# ESP32_XPID.net
KiCad netlist of a schematic drawn in Altium Designer
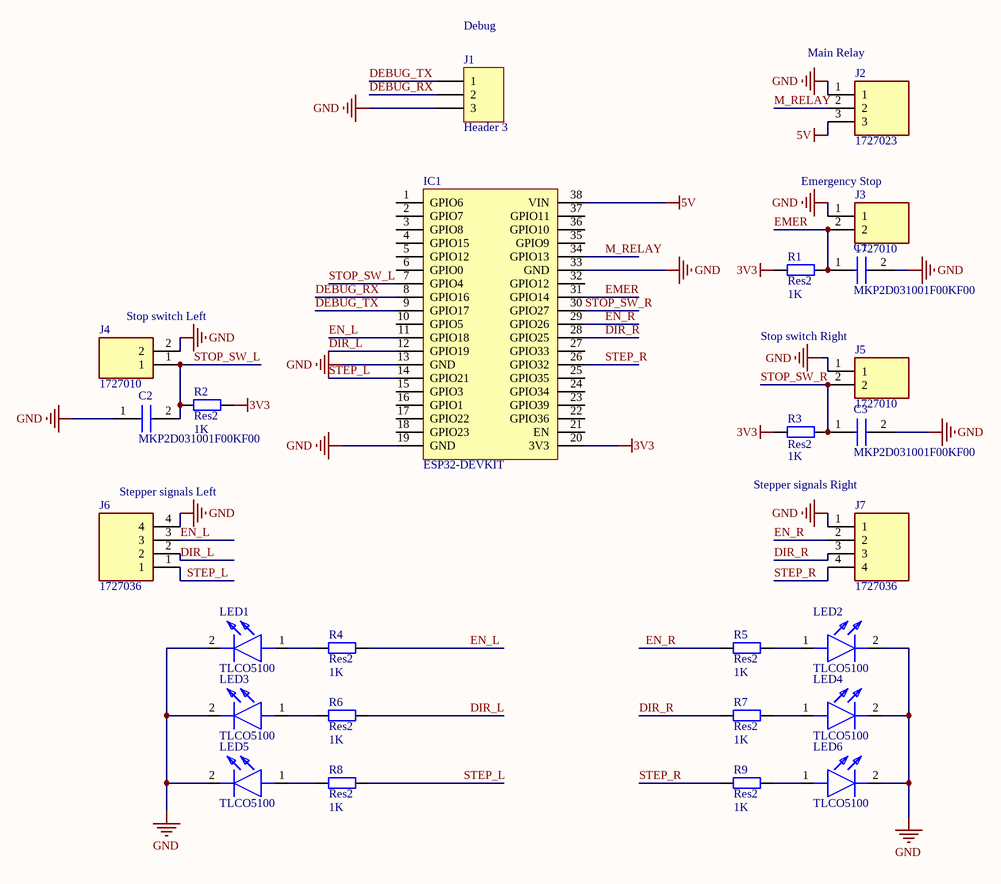
[diagram p0: ESP32_XPID.SchDoc]

(export (version "E")
  (design (tool "Eeschema 10.0.6"))
  (components
    (comp (ref "C1")
      (value "MKP2D031001F00KF00")
      (footprint "SamacSys:MKP2D031001F00KF00")
      (description "Capacitor")
      (fields (field (name "MOUSER PART NUMBER") "505-MKP2D031001F00KF"))
      (libsource (lib "*") (part "MKP2D031001F00KF00"))
    )
    (comp (ref "C2")
      (value "MKP2D031001F00KF00")
      (footprint "SamacSys:MKP2D031001F00KF00")
      (description "Capacitor")
      (fields (field (name "MOUSER PART NUMBER") "505-MKP2D031001F00KF"))
      (libsource (lib "*") (part "MKP2D031001F00KF00"))
    )
    (comp (ref "C3")
      (value "MKP2D031001F00KF00")
      (footprint "SamacSys:MKP2D031001F00KF00")
      (description "Capacitor")
      (fields (field (name "MOUSER PART NUMBER") "505-MKP2D031001F00KF"))
      (libsource (lib "*") (part "MKP2D031001F00KF00"))
    )
    (comp (ref "IC1")
      (value "ESP32-DEVKIT")
      (footprint "NODEMCU-32S")
      (description "NODE-MCU ESP32 development kit")
      (libsource (lib "ESP32_XPID") (part "NODE-MCU-32S"))
    )
    (comp (ref "J1")
      (value "Header 3")
      (footprint "HDR1X3")
      (description "Header, 3-Pin")
      (fields (field (name "PUBLISHER") "Altium Limited"))
      (libsource (lib "Miscellaneous Connectors") (part "Header 3"))
    )
    (comp (ref "J2")
      (value "1727023")
      (footprint "SamacSys:1727023")
      (description "Connector")
      (fields (field (name "MOUSER PART NUMBER") "651-1727023"))
      (libsource (lib "*") (part "1727023"))
    )
    (comp (ref "J3")
      (value "1727010")
      (footprint "SamacSys:1727010")
      (description "Connector")
      (fields (field (name "MOUSER PART NUMBER") "651-1727010"))
      (libsource (lib "*") (part "1727010"))
    )
    (comp (ref "J4")
      (value "1727010")
      (footprint "SamacSys:1727010")
      (description "Connector")
      (fields (field (name "MOUSER PART NUMBER") "651-1727010"))
      (libsource (lib "") (part "1727010_1"))
    )
    (comp (ref "J5")
      (value "1727010")
      (footprint "SamacSys:1727010")
      (description "Connector")
      (fields (field (name "MOUSER PART NUMBER") "651-1727010"))
      (libsource (lib "*") (part "1727010"))
    )
    (comp (ref "J6")
      (value "1727036")
      (footprint "SamacSys:SHDR4W105P0X381_1X4_1523X730X865P")
      (description "Connector")
      (fields (field (name "MOUSER PART NUMBER") "651-1727036"))
      (libsource (lib "") (part "1727036_1"))
    )
    (comp (ref "J7")
      (value "1727036")
      (footprint "SamacSys:SHDR4W105P0X381_1X4_1523X730X865P")
      (description "Connector")
      (fields (field (name "MOUSER PART NUMBER") "651-1727036"))
      (libsource (lib "*") (part "1727036"))
    )
    (comp (ref "LED1")
      (value "TLCO5100")
      (footprint "SamacSys:TLCO5100")
      (description "LED")
      (fields (field (name "MOUSER PART NUMBER") "78-TLCO5100"))
      (libsource (lib "*") (part "TLCO5100"))
    )
    (comp (ref "LED2")
      (value "TLCO5100")
      (footprint "SamacSys:TLCO5100")
      (description "LED")
      (fields (field (name "MOUSER PART NUMBER") "78-TLCO5100"))
      (libsource (lib "*") (part "TLCO5100"))
    )
    (comp (ref "LED3")
      (value "TLCO5100")
      (footprint "SamacSys:TLCO5100")
      (description "LED")
      (fields (field (name "MOUSER PART NUMBER") "78-TLCO5100"))
      (libsource (lib "*") (part "TLCO5100"))
    )
    (comp (ref "LED4")
      (value "TLCO5100")
      (footprint "SamacSys:TLCO5100")
      (description "LED")
      (fields (field (name "MOUSER PART NUMBER") "78-TLCO5100"))
      (libsource (lib "*") (part "TLCO5100"))
    )
    (comp (ref "LED5")
      (value "TLCO5100")
      (footprint "SamacSys:TLCO5100")
      (description "LED")
      (fields (field (name "MOUSER PART NUMBER") "78-TLCO5100"))
      (libsource (lib "*") (part "TLCO5100"))
    )
    (comp (ref "LED6")
      (value "TLCO5100")
      (footprint "SamacSys:TLCO5100")
      (description "LED")
      (fields (field (name "MOUSER PART NUMBER") "78-TLCO5100"))
      (libsource (lib "*") (part "TLCO5100"))
    )
    (comp (ref "R1")
      (value "Res2")
      (footprint "AXIAL-0.4")
      (description "Resistor")
      (fields (field (name "ALTIUM_VALUE") "1K") (field (name "PUBLISHER") "Altium Limited"))
      (libsource (lib "Miscellaneous Devices") (part "Res2"))
    )
    (comp (ref "R2")
      (value "Res2")
      (footprint "AXIAL-0.4")
      (description "Resistor")
      (fields (field (name "ALTIUM_VALUE") "1K") (field (name "PUBLISHER") "Altium Limited"))
      (libsource (lib "Miscellaneous Devices") (part "Res2"))
    )
    (comp (ref "R3")
      (value "Res2")
      (footprint "AXIAL-0.4")
      (description "Resistor")
      (fields (field (name "ALTIUM_VALUE") "1K") (field (name "PUBLISHER") "Altium Limited"))
      (libsource (lib "Miscellaneous Devices") (part "Res2"))
    )
    (comp (ref "R4")
      (value "Res2")
      (footprint "AXIAL-0.4")
      (description "Resistor")
      (fields (field (name "ALTIUM_VALUE") "1K") (field (name "PUBLISHER") "Altium Limited"))
      (libsource (lib "") (part "Res2_1"))
    )
    (comp (ref "R5")
      (value "Res2")
      (footprint "AXIAL-0.4")
      (description "Resistor")
      (fields (field (name "ALTIUM_VALUE") "1K") (field (name "PUBLISHER") "Altium Limited"))
      (libsource (lib "Miscellaneous Devices") (part "Res2"))
    )
    (comp (ref "R6")
      (value "Res2")
      (footprint "AXIAL-0.4")
      (description "Resistor")
      (fields (field (name "ALTIUM_VALUE") "1K") (field (name "PUBLISHER") "Altium Limited"))
      (libsource (lib "") (part "Res2_1"))
    )
    (comp (ref "R7")
      (value "Res2")
      (footprint "AXIAL-0.4")
      (description "Resistor")
      (fields (field (name "ALTIUM_VALUE") "1K") (field (name "PUBLISHER") "Altium Limited"))
      (libsource (lib "Miscellaneous Devices") (part "Res2"))
    )
    (comp (ref "R8")
      (value "Res2")
      (footprint "AXIAL-0.4")
      (description "Resistor")
      (fields (field (name "ALTIUM_VALUE") "1K") (field (name "PUBLISHER") "Altium Limited"))
      (libsource (lib "") (part "Res2_1"))
    )
    (comp (ref "R9")
      (value "Res2")
      (footprint "AXIAL-0.4")
      (description "Resistor")
      (fields (field (name "ALTIUM_VALUE") "1K") (field (name "PUBLISHER") "Altium Limited"))
      (libsource (lib "Miscellaneous Devices") (part "Res2"))
    )
  )
  (nets
    (net (code "1") (name "/DEBUG_RX") (class "Default")
      (node (ref "IC1") (pin "8") (pinfunction "GPIO16_8") (pintype "passive"))
      (node (ref "J1") (pin "2") (pinfunction "2_2") (pintype "passive"))
    )
    (net (code "2") (name "/DEBUG_TX") (class "Default")
      (node (ref "IC1") (pin "9") (pinfunction "GPIO17_9") (pintype "passive"))
      (node (ref "J1") (pin "1") (pinfunction "1_1") (pintype "passive"))
    )
    (net (code "3") (name "/DIR_L") (class "Default")
      (node (ref "IC1") (pin "12") (pinfunction "GPIO19_12") (pintype "passive"))
      (node (ref "J6") (pin "2") (pinfunction "2_2") (pintype "passive"))
      (node (ref "R6") (pin "1") (pinfunction "1_1") (pintype "passive"))
    )
    (net (code "4") (name "/DIR_R") (class "Default")
      (node (ref "IC1") (pin "28") (pinfunction "GPIO25_28") (pintype "passive"))
      (node (ref "J7") (pin "3") (pinfunction "3_3") (pintype "passive"))
      (node (ref "R7") (pin "1") (pinfunction "1_1") (pintype "passive"))
    )
    (net (code "5") (name "/EMER") (class "Default")
      (node (ref "C1") (pin "1") (pinfunction "1_1") (pintype "passive"))
      (node (ref "IC1") (pin "31") (pinfunction "GPIO14_31") (pintype "passive"))
      (node (ref "J3") (pin "2") (pinfunction "2_2") (pintype "passive"))
      (node (ref "R1") (pin "2") (pinfunction "2_2") (pintype "passive"))
    )
    (net (code "6") (name "/EN_L") (class "Default")
      (node (ref "IC1") (pin "11") (pinfunction "GPIO18_11") (pintype "passive"))
      (node (ref "J6") (pin "3") (pinfunction "3_3") (pintype "passive"))
      (node (ref "R4") (pin "1") (pinfunction "1_1") (pintype "passive"))
    )
    (net (code "7") (name "/EN_R") (class "Default")
      (node (ref "IC1") (pin "29") (pinfunction "GPIO26_29") (pintype "passive"))
      (node (ref "J7") (pin "2") (pinfunction "2_2") (pintype "passive"))
      (node (ref "R5") (pin "1") (pinfunction "1_1") (pintype "passive"))
    )
    (net (code "8") (name "/M_RELAY") (class "Default")
      (node (ref "IC1") (pin "34") (pinfunction "GPIO13_34") (pintype "passive"))
      (node (ref "J2") (pin "2") (pinfunction "2_2") (pintype "passive"))
    )
    (net (code "9") (name "/STEP_L") (class "Default")
      (node (ref "IC1") (pin "14") (pinfunction "GPIO21_14") (pintype "passive"))
      (node (ref "J6") (pin "1") (pinfunction "1_1") (pintype "passive"))
      (node (ref "R8") (pin "1") (pinfunction "1_1") (pintype "passive"))
    )
    (net (code "10") (name "/STEP_R") (class "Default")
      (node (ref "IC1") (pin "26") (pinfunction "GPIO32_26") (pintype "passive"))
      (node (ref "J7") (pin "4") (pinfunction "4_4") (pintype "passive"))
      (node (ref "R9") (pin "1") (pinfunction "1_1") (pintype "passive"))
    )
    (net (code "11") (name "/STOP_SW_L") (class "Default")
      (node (ref "C2") (pin "2") (pinfunction "2_2") (pintype "passive"))
      (node (ref "IC1") (pin "7") (pinfunction "GPIO4_7") (pintype "passive"))
      (node (ref "J4") (pin "1") (pinfunction "1_1") (pintype "passive"))
      (node (ref "R2") (pin "1") (pinfunction "1_1") (pintype "passive"))
    )
    (net (code "12") (name "/STOP_SW_R") (class "Default")
      (node (ref "C3") (pin "1") (pinfunction "1_1") (pintype "passive"))
      (node (ref "IC1") (pin "30") (pinfunction "GPIO27_30") (pintype "passive"))
      (node (ref "J5") (pin "2") (pinfunction "2_2") (pintype "passive"))
      (node (ref "R3") (pin "2") (pinfunction "2_2") (pintype "passive"))
    )
    (net (code "13") (name "3V3") (class "Default")
      (node (ref "IC1") (pin "20") (pinfunction "3V3_20") (pintype "passive"))
      (node (ref "R1") (pin "1") (pinfunction "1_1") (pintype "passive"))
      (node (ref "R2") (pin "2") (pinfunction "2_2") (pintype "passive"))
      (node (ref "R3") (pin "1") (pinfunction "1_1") (pintype "passive"))
    )
    (net (code "14") (name "5V") (class "Default")
      (node (ref "IC1") (pin "38") (pinfunction "VIN_38") (pintype "passive"))
      (node (ref "J2") (pin "3") (pinfunction "3_3") (pintype "passive"))
    )
    (net (code "15") (name "GND") (class "Default")
      (node (ref "C1") (pin "2") (pinfunction "2_2") (pintype "passive"))
      (node (ref "C2") (pin "1") (pinfunction "1_1") (pintype "passive"))
      (node (ref "C3") (pin "2") (pinfunction "2_2") (pintype "passive"))
      (node (ref "IC1") (pin "13") (pinfunction "GND_13") (pintype "passive"))
      (node (ref "IC1") (pin "19") (pinfunction "GND_19") (pintype "passive"))
      (node (ref "IC1") (pin "33") (pinfunction "GND_33") (pintype "passive"))
      (node (ref "J1") (pin "3") (pinfunction "3_3") (pintype "passive"))
      (node (ref "J2") (pin "1") (pinfunction "1_1") (pintype "passive"))
      (node (ref "J3") (pin "1") (pinfunction "1_1") (pintype "passive"))
      (node (ref "J4") (pin "2") (pinfunction "2_2") (pintype "passive"))
      (node (ref "J5") (pin "1") (pinfunction "1_1") (pintype "passive"))
      (node (ref "J6") (pin "4") (pinfunction "4_4") (pintype "passive"))
      (node (ref "J7") (pin "1") (pinfunction "1_1") (pintype "passive"))
      (node (ref "LED1") (pin "2") (pinfunction "K_2") (pintype "passive"))
      (node (ref "LED2") (pin "2") (pinfunction "K_2") (pintype "passive"))
      (node (ref "LED3") (pin "2") (pinfunction "K_2") (pintype "passive"))
      (node (ref "LED4") (pin "2") (pinfunction "K_2") (pintype "passive"))
      (node (ref "LED5") (pin "2") (pinfunction "K_2") (pintype "passive"))
      (node (ref "LED6") (pin "2") (pinfunction "K_2") (pintype "passive"))
    )
    (net (code "16") (name "Net-(LED1-A)") (class "Default")
      (node (ref "LED1") (pin "1") (pinfunction "A_1") (pintype "passive"))
      (node (ref "R4") (pin "2") (pinfunction "2_2") (pintype "passive"))
    )
    (net (code "17") (name "Net-(LED2-A)") (class "Default")
      (node (ref "LED2") (pin "1") (pinfunction "A_1") (pintype "passive"))
      (node (ref "R5") (pin "2") (pinfunction "2_2") (pintype "passive"))
    )
    (net (code "18") (name "Net-(LED3-A)") (class "Default")
      (node (ref "LED3") (pin "1") (pinfunction "A_1") (pintype "passive"))
      (node (ref "R6") (pin "2") (pinfunction "2_2") (pintype "passive"))
    )
    (net (code "19") (name "Net-(LED4-A)") (class "Default")
      (node (ref "LED4") (pin "1") (pinfunction "A_1") (pintype "passive"))
      (node (ref "R7") (pin "2") (pinfunction "2_2") (pintype "passive"))
    )
    (net (code "20") (name "Net-(LED5-A)") (class "Default")
      (node (ref "LED5") (pin "1") (pinfunction "A_1") (pintype "passive"))
      (node (ref "R8") (pin "2") (pinfunction "2_2") (pintype "passive"))
    )
    (net (code "21") (name "Net-(LED6-A)") (class "Default")
      (node (ref "LED6") (pin "1") (pinfunction "A_1") (pintype "passive"))
      (node (ref "R9") (pin "2") (pinfunction "2_2") (pintype "passive"))
    )
    (net (code "22") (name "unconnected-(IC1-EN-Pad21)") (class "Default")
      (node (ref "IC1") (pin "21") (pinfunction "EN_21") (pintype "passive"))
    )
    (net (code "23") (name "unconnected-(IC1-GPIO0-Pad6)") (class "Default")
      (node (ref "IC1") (pin "6") (pinfunction "GPIO0_6") (pintype "passive"))
    )
    (net (code "24") (name "unconnected-(IC1-GPIO1-Pad16)") (class "Default")
      (node (ref "IC1") (pin "16") (pinfunction "GPIO1_16") (pintype "passive"))
    )
    (net (code "25") (name "unconnected-(IC1-GPIO3-Pad15)") (class "Default")
      (node (ref "IC1") (pin "15") (pinfunction "GPIO3_15") (pintype "passive"))
    )
    (net (code "26") (name "unconnected-(IC1-GPIO5-Pad10)") (class "Default")
      (node (ref "IC1") (pin "10") (pinfunction "GPIO5_10") (pintype "passive"))
    )
    (net (code "27") (name "unconnected-(IC1-GPIO6-Pad1)") (class "Default")
      (node (ref "IC1") (pin "1") (pinfunction "GPIO6_1") (pintype "passive"))
    )
    (net (code "28") (name "unconnected-(IC1-GPIO7-Pad2)") (class "Default")
      (node (ref "IC1") (pin "2") (pinfunction "GPIO7_2") (pintype "passive"))
    )
    (net (code "29") (name "unconnected-(IC1-GPIO8-Pad3)") (class "Default")
      (node (ref "IC1") (pin "3") (pinfunction "GPIO8_3") (pintype "passive"))
    )
    (net (code "30") (name "unconnected-(IC1-GPIO9-Pad35)") (class "Default")
      (node (ref "IC1") (pin "35") (pinfunction "GPIO9_35") (pintype "passive"))
    )
    (net (code "31") (name "unconnected-(IC1-GPIO10-Pad36)") (class "Default")
      (node (ref "IC1") (pin "36") (pinfunction "GPIO10_36") (pintype "passive"))
    )
    (net (code "32") (name "unconnected-(IC1-GPIO11-Pad37)") (class "Default")
      (node (ref "IC1") (pin "37") (pinfunction "GPIO11_37") (pintype "passive"))
    )
    (net (code "33") (name "unconnected-(IC1-GPIO12-Pad5)") (class "Default")
      (node (ref "IC1") (pin "5") (pinfunction "GPIO12_5") (pintype "passive"))
    )
    (net (code "34") (name "unconnected-(IC1-GPIO12-Pad32)") (class "Default")
      (node (ref "IC1") (pin "32") (pinfunction "GPIO12_32") (pintype "passive"))
    )
    (net (code "35") (name "unconnected-(IC1-GPIO15-Pad4)") (class "Default")
      (node (ref "IC1") (pin "4") (pinfunction "GPIO15_4") (pintype "passive"))
    )
    (net (code "36") (name "unconnected-(IC1-GPIO22-Pad17)") (class "Default")
      (node (ref "IC1") (pin "17") (pinfunction "GPIO22_17") (pintype "passive"))
    )
    (net (code "37") (name "unconnected-(IC1-GPIO23-Pad18)") (class "Default")
      (node (ref "IC1") (pin "18") (pinfunction "GPIO23_18") (pintype "passive"))
    )
    (net (code "38") (name "unconnected-(IC1-GPIO33-Pad27)") (class "Default")
      (node (ref "IC1") (pin "27") (pinfunction "GPIO33_27") (pintype "passive"))
    )
    (net (code "39") (name "unconnected-(IC1-GPIO34-Pad24)") (class "Default")
      (node (ref "IC1") (pin "24") (pinfunction "GPIO34_24") (pintype "passive"))
    )
    (net (code "40") (name "unconnected-(IC1-GPIO35-Pad25)") (class "Default")
      (node (ref "IC1") (pin "25") (pinfunction "GPIO35_25") (pintype "passive"))
    )
    (net (code "41") (name "unconnected-(IC1-GPIO36-Pad22)") (class "Default")
      (node (ref "IC1") (pin "22") (pinfunction "GPIO36_22") (pintype "passive"))
    )
    (net (code "42") (name "unconnected-(IC1-GPIO39-Pad23)") (class "Default")
      (node (ref "IC1") (pin "23") (pinfunction "GPIO39_23") (pintype "passive"))
    )
  )
)
